# n20__TEST.net
KiCad netlist of a schematic drawn in Altium Designer
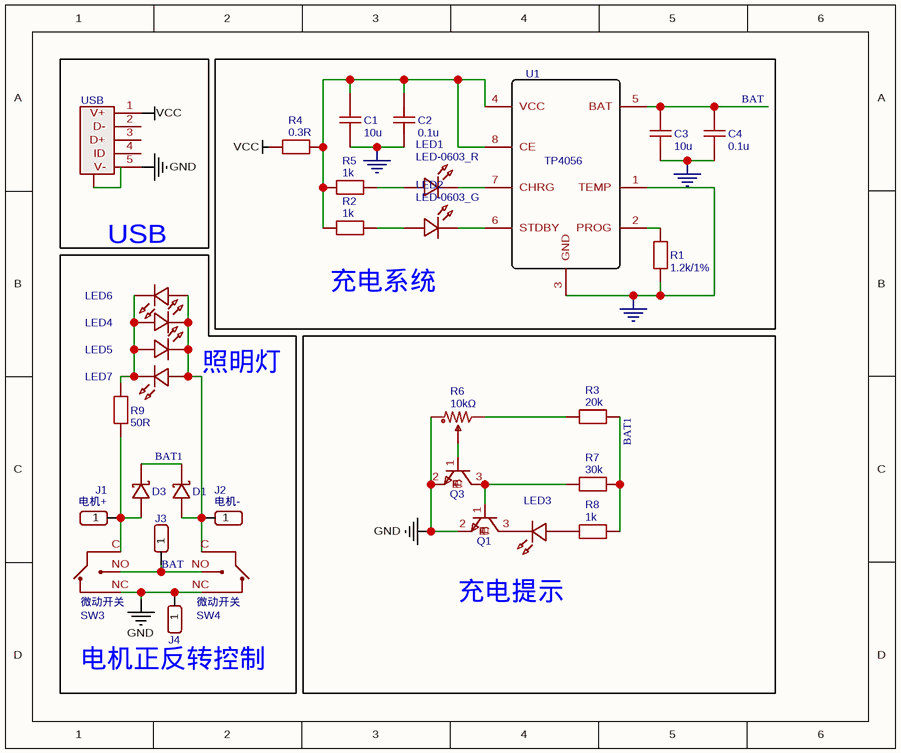
[diagram p0: n20电动螺丝刀_TEST（测试用！！！）.schdoc]

(export (version "E")
  (design (tool "Eeschema 10.0.6"))
  (components
    (comp (ref "C1")
      (value "10u")
      (fields (field (name "CONTRIBUTOR") "LCEDA_Lib"))
      (libsource (lib "altium-import") (part "root_1_10u_"))
    )
    (comp (ref "C2")
      (value "0.1u")
      (fields (field (name "CONTRIBUTOR") "LCEDA_Lib"))
      (libsource (lib "altium-import") (part "root_1_0.1u_"))
    )
    (comp (ref "C3")
      (value "10u")
      (fields (field (name "CONTRIBUTOR") "LCEDA_Lib"))
      (libsource (lib "altium-import") (part "root_1_10u_"))
    )
    (comp (ref "C4")
      (value "0.1u")
      (fields (field (name "CONTRIBUTOR") "LCEDA_Lib"))
      (libsource (lib "altium-import") (part "root_1_0.1u_"))
    )
    (comp (ref "D1")
      (value "1N5817WS")
      (fields (field (name "BOM_SUPPLIER PART") "C489146") (field (name "CONTRIBUTOR") "LCSC"))
      (libsource (lib "altium-import") (part "root_3_1N5817WS_"))
    )
    (comp (ref "D3")
      (value "1N5817WS")
      (fields (field (name "BOM_SUPPLIER PART") "C489146") (field (name "CONTRIBUTOR") "LCSC"))
      (libsource (lib "altium-import") (part "root_3_1N5817WS_"))
    )
    (comp (ref "J1")
      (value "电机+")
      (fields (field (name "BOM_SUPPLIER PART") "C81276") (field (name "CONTRIBUTOR") "LCEDA_Lib"))
      (libsource (lib "altium-import") (part "root_0_电机+_"))
    )
    (comp (ref "J2")
      (value "电机-")
      (fields (field (name "BOM_SUPPLIER PART") "C81276") (field (name "CONTRIBUTOR") "LCEDA_Lib"))
      (libsource (lib "altium-import") (part "root_0_电机-_"))
    )
    (comp (ref "J3")
      (value "HDR-M-2.54_1x1")
      (fields (field (name "BOM_SUPPLIER PART") "C81276") (field (name "CONTRIBUTOR") "LCEDA_Lib"))
      (libsource (lib "altium-import") (part "root_1_HDR-M-2.54_1x1_"))
    )
    (comp (ref "J4")
      (value "HDR-M-2.54_1x1")
      (fields (field (name "BOM_SUPPLIER PART") "C81276") (field (name "CONTRIBUTOR") "LCEDA_Lib"))
      (libsource (lib "altium-import") (part "root_3_HDR-M-2.54_1x1_"))
    )
    (comp (ref "LED1")
      (value "LED-0603_R")
      (fields
        (field (name "BOM_MANUFACTURER PART") "19-217/R6C-AL1M2VY/3T")
        (field (name "BOM_SUPPLIER PART") "C72044")
        (field (name "CONTRIBUTOR") "LCEDA_01")
      )
      (libsource (lib "altium-import") (part "root_0_LED-0603_R_"))
    )
    (comp (ref "LED2")
      (value "LED-0603_G")
      (fields
        (field (name "BOM_MANUFACTURER PART") "19-217/GHC-YR1S2/3T")
        (field (name "BOM_SUPPLIER PART") "C72043")
        (field (name "CONTRIBUTOR") "LCEDA_Lib")
      )
      (libsource (lib "altium-import") (part "root_0_LED-0603_G_"))
    )
    (comp (ref "LED3")
      (value "LED-0603_R")
      (fields
        (field (name "BOM_MANUFACTURER PART") "19-217/R6C-AL1M2VY/3T")
        (field (name "BOM_SUPPLIER PART") "C72044")
        (field (name "CONTRIBUTOR") "LCEDA_01")
      )
      (libsource (lib "altium-import") (part "root_2_LED-0603_R_"))
    )
    (comp (ref "LED4")
      (value "LED-0603_R")
      (fields
        (field (name "BOM_MANUFACTURER PART") "19-217/R6C-AL1M2VY/3T")
        (field (name "BOM_SUPPLIER PART") "C72044")
        (field (name "CONTRIBUTOR") "LCEDA_01")
      )
      (libsource (lib "altium-import") (part "root_0_LED-0603_R_"))
    )
    (comp (ref "LED5")
      (value "LED-0603_R")
      (fields
        (field (name "BOM_MANUFACTURER PART") "19-217/R6C-AL1M2VY/3T")
        (field (name "BOM_SUPPLIER PART") "C72044")
        (field (name "CONTRIBUTOR") "LCEDA_01")
      )
      (libsource (lib "altium-import") (part "root_0_LED-0603_R_"))
    )
    (comp (ref "LED6")
      (value "LED-0603_R")
      (fields
        (field (name "BOM_MANUFACTURER PART") "19-217/R6C-AL1M2VY/3T")
        (field (name "BOM_SUPPLIER PART") "C72044")
        (field (name "CONTRIBUTOR") "LCEDA_01")
      )
      (libsource (lib "altium-import") (part "root_2_LED-0603_R_"))
    )
    (comp (ref "LED7")
      (value "LED-0603_R")
      (fields
        (field (name "BOM_MANUFACTURER PART") "19-217/R6C-AL1M2VY/3T")
        (field (name "BOM_SUPPLIER PART") "C72044")
        (field (name "CONTRIBUTOR") "LCEDA_01")
      )
      (libsource (lib "altium-import") (part "root_2_LED-0603_R_"))
    )
    (comp (ref "Q1")
      (value "S8050_C2926165")
      (fields
        (field (name "BOM_SUPPLIER PART") "C2926165")
        (field (name "BOM_MANUFACTURER PART") "S8050")
        (field (name "CONTRIBUTOR") "LCSC")
      )
      (libsource (lib "altium-import") (part "root_3_S8050_C2926165_"))
    )
    (comp (ref "Q3")
      (value "S8050_C2926165")
      (fields
        (field (name "BOM_SUPPLIER PART") "C2926165")
        (field (name "BOM_MANUFACTURER PART") "S8050")
        (field (name "CONTRIBUTOR") "LCSC")
      )
      (libsource (lib "altium-import") (part "root_3_S8050_C2926165_"))
    )
    (comp (ref "R1")
      (value "1.2k/1%")
      (fields (field (name "CONTRIBUTOR") "LCEDA_Lib"))
      (libsource (lib "altium-import") (part "root_1_1.2k/1%_"))
    )
    (comp (ref "R2")
      (value "1k")
      (fields (field (name "CONTRIBUTOR") "LCEDA_Lib"))
      (libsource (lib "altium-import") (part "root_0_1k_"))
    )
    (comp (ref "R3")
      (value "20k")
      (fields (field (name "CONTRIBUTOR") "LCEDA_Lib"))
      (libsource (lib "altium-import") (part "root_0_20k_"))
    )
    (comp (ref "R4")
      (value "0.3R")
      (fields (field (name "CONTRIBUTOR") "LCEDA_Lib"))
      (libsource (lib "altium-import") (part "root_0_0.3R_"))
    )
    (comp (ref "R5")
      (value "1k")
      (fields (field (name "CONTRIBUTOR") "LCEDA_Lib"))
      (libsource (lib "altium-import") (part "root_0_1k_"))
    )
    (comp (ref "R6")
      (value "10kΩ")
      (fields
        (field (name "BOM_SUPPLIER PART") "C719176")
        (field (name "BOM_MANUFACTURER PART") "TC33X-2-103E")
        (field (name "CONTRIBUTOR") "LCSC")
      )
      (libsource (lib "altium-import") (part "root_2_10kΩ_"))
    )
    (comp (ref "R7")
      (value "30k")
      (fields (field (name "CONTRIBUTOR") "LCEDA_Lib"))
      (libsource (lib "altium-import") (part "root_0_30k_"))
    )
    (comp (ref "R8")
      (value "1k")
      (fields (field (name "CONTRIBUTOR") "LCEDA_Lib"))
      (libsource (lib "altium-import") (part "root_0_1k_"))
    )
    (comp (ref "R9")
      (value "50R")
      (fields (field (name "CONTRIBUTOR") "LCEDA_Lib"))
      (libsource (lib "altium-import") (part "root_1_50R_"))
    )
    (comp (ref "SW3")
      (value "微动开关")
      (fields
        (field (name "BOM_SUPPLIER PART") "C2914466")
        (field (name "BOM_MANUFACTURER PART") "LF-108")
        (field (name "CONTRIBUTOR") "LCSC")
      )
      (libsource (lib "") (part "root_1_微动开关__1"))
    )
    (comp (ref "SW4")
      (value "微动开关")
      (fields
        (field (name "BOM_SUPPLIER PART") "C2914466")
        (field (name "BOM_MANUFACTURER PART") "LF-108")
        (field (name "CONTRIBUTOR") "LCSC")
      )
      (libsource (lib "altium-import") (part "root_1_微动开关_"))
    )
    (comp (ref "U1") (value "TP4056") (libsource (lib "altium-import") (part "root_0_TP4056_")))
    (comp (ref "USB")
      (value "micro 5PFour-legged board7.2There is a column card point0.4m")
      (fields (field (name "BOM_SUPPLIER PART") "C40943"))
      (libsource (lib "altium-import") (part "root_0_micro 5PFour-legged board7.2There is a column card point0.4m_"))
    )
  )
  (nets
    (net (code "1") (name "/BAT") (class "Default")
      (node (ref "C3") (pin "2") (pinfunction "2_2") (pintype "passive"))
      (node (ref "C4") (pin "2") (pinfunction "2_2") (pintype "passive"))
      (node (ref "J3") (pin "1") (pinfunction "1_1") (pintype "passive"))
      (node (ref "SW3") (pin "NO") (pinfunction "NO_NO") (pintype "passive"))
      (node (ref "SW4") (pin "NO") (pinfunction "NO_NO") (pintype "passive"))
      (node (ref "U1") (pin "5") (pinfunction "BAT_5") (pintype "passive"))
    )
    (net (code "2") (name "/BAT1") (class "Default")
      (node (ref "D1") (pin "1") (pinfunction "1_1") (pintype "passive"))
      (node (ref "D3") (pin "1") (pinfunction "1_1") (pintype "passive"))
      (node (ref "R3") (pin "2") (pinfunction "2_2") (pintype "passive"))
      (node (ref "R7") (pin "2") (pinfunction "2_2") (pintype "passive"))
      (node (ref "R8") (pin "2") (pinfunction "2_2") (pintype "passive"))
    )
    (net (code "3") (name "GND") (class "Default")
      (node (ref "C1") (pin "1") (pinfunction "1_1") (pintype "passive"))
      (node (ref "C2") (pin "1") (pinfunction "1_1") (pintype "passive"))
      (node (ref "C3") (pin "1") (pinfunction "1_1") (pintype "passive"))
      (node (ref "C4") (pin "1") (pinfunction "1_1") (pintype "passive"))
      (node (ref "J4") (pin "1") (pinfunction "1_1") (pintype "passive"))
      (node (ref "Q1") (pin "2") (pinfunction "E_2") (pintype "passive"))
      (node (ref "Q3") (pin "2") (pinfunction "E_2") (pintype "passive"))
      (node (ref "R1") (pin "1") (pinfunction "1_1") (pintype "passive"))
      (node (ref "R6") (pin "1") (pinfunction "1_1") (pintype "passive"))
      (node (ref "SW3") (pin "NC") (pinfunction "NC_NC") (pintype "passive"))
      (node (ref "SW4") (pin "NC") (pinfunction "NC_NC") (pintype "passive"))
      (node (ref "U1") (pin "1") (pinfunction "TEMP_1") (pintype "passive"))
      (node (ref "U1") (pin "3") (pinfunction "GND_3") (pintype "passive"))
      (node (ref "USB") (pin "5") (pinfunction "V-_5") (pintype "passive"))
    )
    (net (code "4") (name "Net-(D1-Pad2)") (class "Default")
      (node (ref "D1") (pin "2") (pinfunction "2_2") (pintype "passive"))
      (node (ref "J2") (pin "1") (pinfunction "1_1") (pintype "passive"))
      (node (ref "LED4") (pin "2") (pinfunction "2_2") (pintype "passive"))
      (node (ref "LED5") (pin "2") (pinfunction "2_2") (pintype "passive"))
      (node (ref "LED6") (pin "1") (pinfunction "1_1") (pintype "passive"))
      (node (ref "LED7") (pin "1") (pinfunction "1_1") (pintype "passive"))
      (node (ref "SW4") (pin "C") (pinfunction "C_C") (pintype "passive"))
    )
    (net (code "5") (name "Net-(D3-Pad2)") (class "Default")
      (node (ref "D3") (pin "2") (pinfunction "2_2") (pintype "passive"))
      (node (ref "J1") (pin "1") (pinfunction "1_1") (pintype "passive"))
      (node (ref "R9") (pin "1") (pinfunction "1_1") (pintype "passive"))
      (node (ref "SW3") (pin "C") (pinfunction "C_C") (pintype "passive"))
    )
    (net (code "6") (name "Net-(LED1-Pad1)") (class "Default")
      (node (ref "LED1") (pin "1") (pinfunction "1_1") (pintype "passive"))
      (node (ref "R5") (pin "2") (pinfunction "2_2") (pintype "passive"))
    )
    (net (code "7") (name "Net-(LED2-Pad1)") (class "Default")
      (node (ref "LED2") (pin "1") (pinfunction "1_1") (pintype "passive"))
      (node (ref "R2") (pin "2") (pinfunction "2_2") (pintype "passive"))
    )
    (net (code "8") (name "Net-(LED3-Pad1)") (class "Default")
      (node (ref "LED3") (pin "1") (pinfunction "1_1") (pintype "passive"))
      (node (ref "R8") (pin "1") (pinfunction "1_1") (pintype "passive"))
    )
    (net (code "9") (name "Net-(LED4-Pad1)") (class "Default")
      (node (ref "LED4") (pin "1") (pinfunction "1_1") (pintype "passive"))
      (node (ref "LED5") (pin "1") (pinfunction "1_1") (pintype "passive"))
      (node (ref "LED6") (pin "2") (pinfunction "2_2") (pintype "passive"))
      (node (ref "LED7") (pin "2") (pinfunction "2_2") (pintype "passive"))
      (node (ref "R9") (pin "2") (pinfunction "2_2") (pintype "passive"))
    )
    (net (code "10") (name "Net-(Q1-B)") (class "Default")
      (node (ref "Q1") (pin "1") (pinfunction "B_1") (pintype "passive"))
      (node (ref "Q3") (pin "3") (pinfunction "C_3") (pintype "passive"))
      (node (ref "R7") (pin "1") (pinfunction "1_1") (pintype "passive"))
    )
    (net (code "11") (name "Net-(Q1-C)") (class "Default")
      (node (ref "LED3") (pin "2") (pinfunction "2_2") (pintype "passive"))
      (node (ref "Q1") (pin "3") (pinfunction "C_3") (pintype "passive"))
    )
    (net (code "12") (name "Net-(Q3-B)") (class "Default")
      (node (ref "Q3") (pin "1") (pinfunction "B_1") (pintype "passive"))
      (node (ref "R6") (pin "2") (pinfunction "2_2") (pintype "passive"))
    )
    (net (code "13") (name "Net-(R3-Pad1)") (class "Default")
      (node (ref "R3") (pin "1") (pinfunction "1_1") (pintype "passive"))
      (node (ref "R6") (pin "3") (pinfunction "3_3") (pintype "passive"))
    )
    (net (code "14") (name "Net-(U1-CE)") (class "Default")
      (node (ref "C1") (pin "2") (pinfunction "2_2") (pintype "passive"))
      (node (ref "C2") (pin "2") (pinfunction "2_2") (pintype "passive"))
      (node (ref "R2") (pin "1") (pinfunction "1_1") (pintype "passive"))
      (node (ref "R4") (pin "2") (pinfunction "2_2") (pintype "passive"))
      (node (ref "R5") (pin "1") (pinfunction "1_1") (pintype "passive"))
      (node (ref "U1") (pin "4") (pinfunction "VCC_4") (pintype "passive"))
      (node (ref "U1") (pin "8") (pinfunction "CE_8") (pintype "passive"))
    )
    (net (code "15") (name "Net-(U1-CHRG)") (class "Default")
      (node (ref "LED1") (pin "2") (pinfunction "2_2") (pintype "passive"))
      (node (ref "U1") (pin "7") (pinfunction "CHRG_7") (pintype "passive"))
    )
    (net (code "16") (name "Net-(U1-PROG)") (class "Default")
      (node (ref "R1") (pin "2") (pinfunction "2_2") (pintype "passive"))
      (node (ref "U1") (pin "2") (pinfunction "PROG_2") (pintype "passive"))
    )
    (net (code "17") (name "Net-(U1-STDBY)") (class "Default")
      (node (ref "LED2") (pin "2") (pinfunction "2_2") (pintype "passive"))
      (node (ref "U1") (pin "6") (pinfunction "STDBY_6") (pintype "passive"))
    )
    (net (code "18") (name "VCC") (class "Default")
      (node (ref "R4") (pin "1") (pinfunction "1_1") (pintype "passive"))
      (node (ref "USB") (pin "1") (pinfunction "V+_1") (pintype "passive"))
    )
    (net (code "19") (name "unconnected-(USB-D+-Pad3)") (class "Default")
      (node (ref "USB") (pin "3") (pinfunction "D+_3") (pintype "passive"))
    )
    (net (code "20") (name "unconnected-(USB-D--Pad2)") (class "Default")
      (node (ref "USB") (pin "2") (pinfunction "D-_2") (pintype "passive"))
    )
    (net (code "21") (name "unconnected-(USB-ID-Pad4)") (class "Default")
      (node (ref "USB") (pin "4") (pinfunction "ID_4") (pintype "passive"))
    )
    (net (code "22") (name "unconnected-(USB-MTN6-Pad0)") (class "Default")
      (node (ref "USB") (pin "0") (pinfunction "MTN6_0") (pintype "passive"))
    )
  )
)
